# Final_Project.net
KiCad netlist of a schematic drawn in Altium Designer
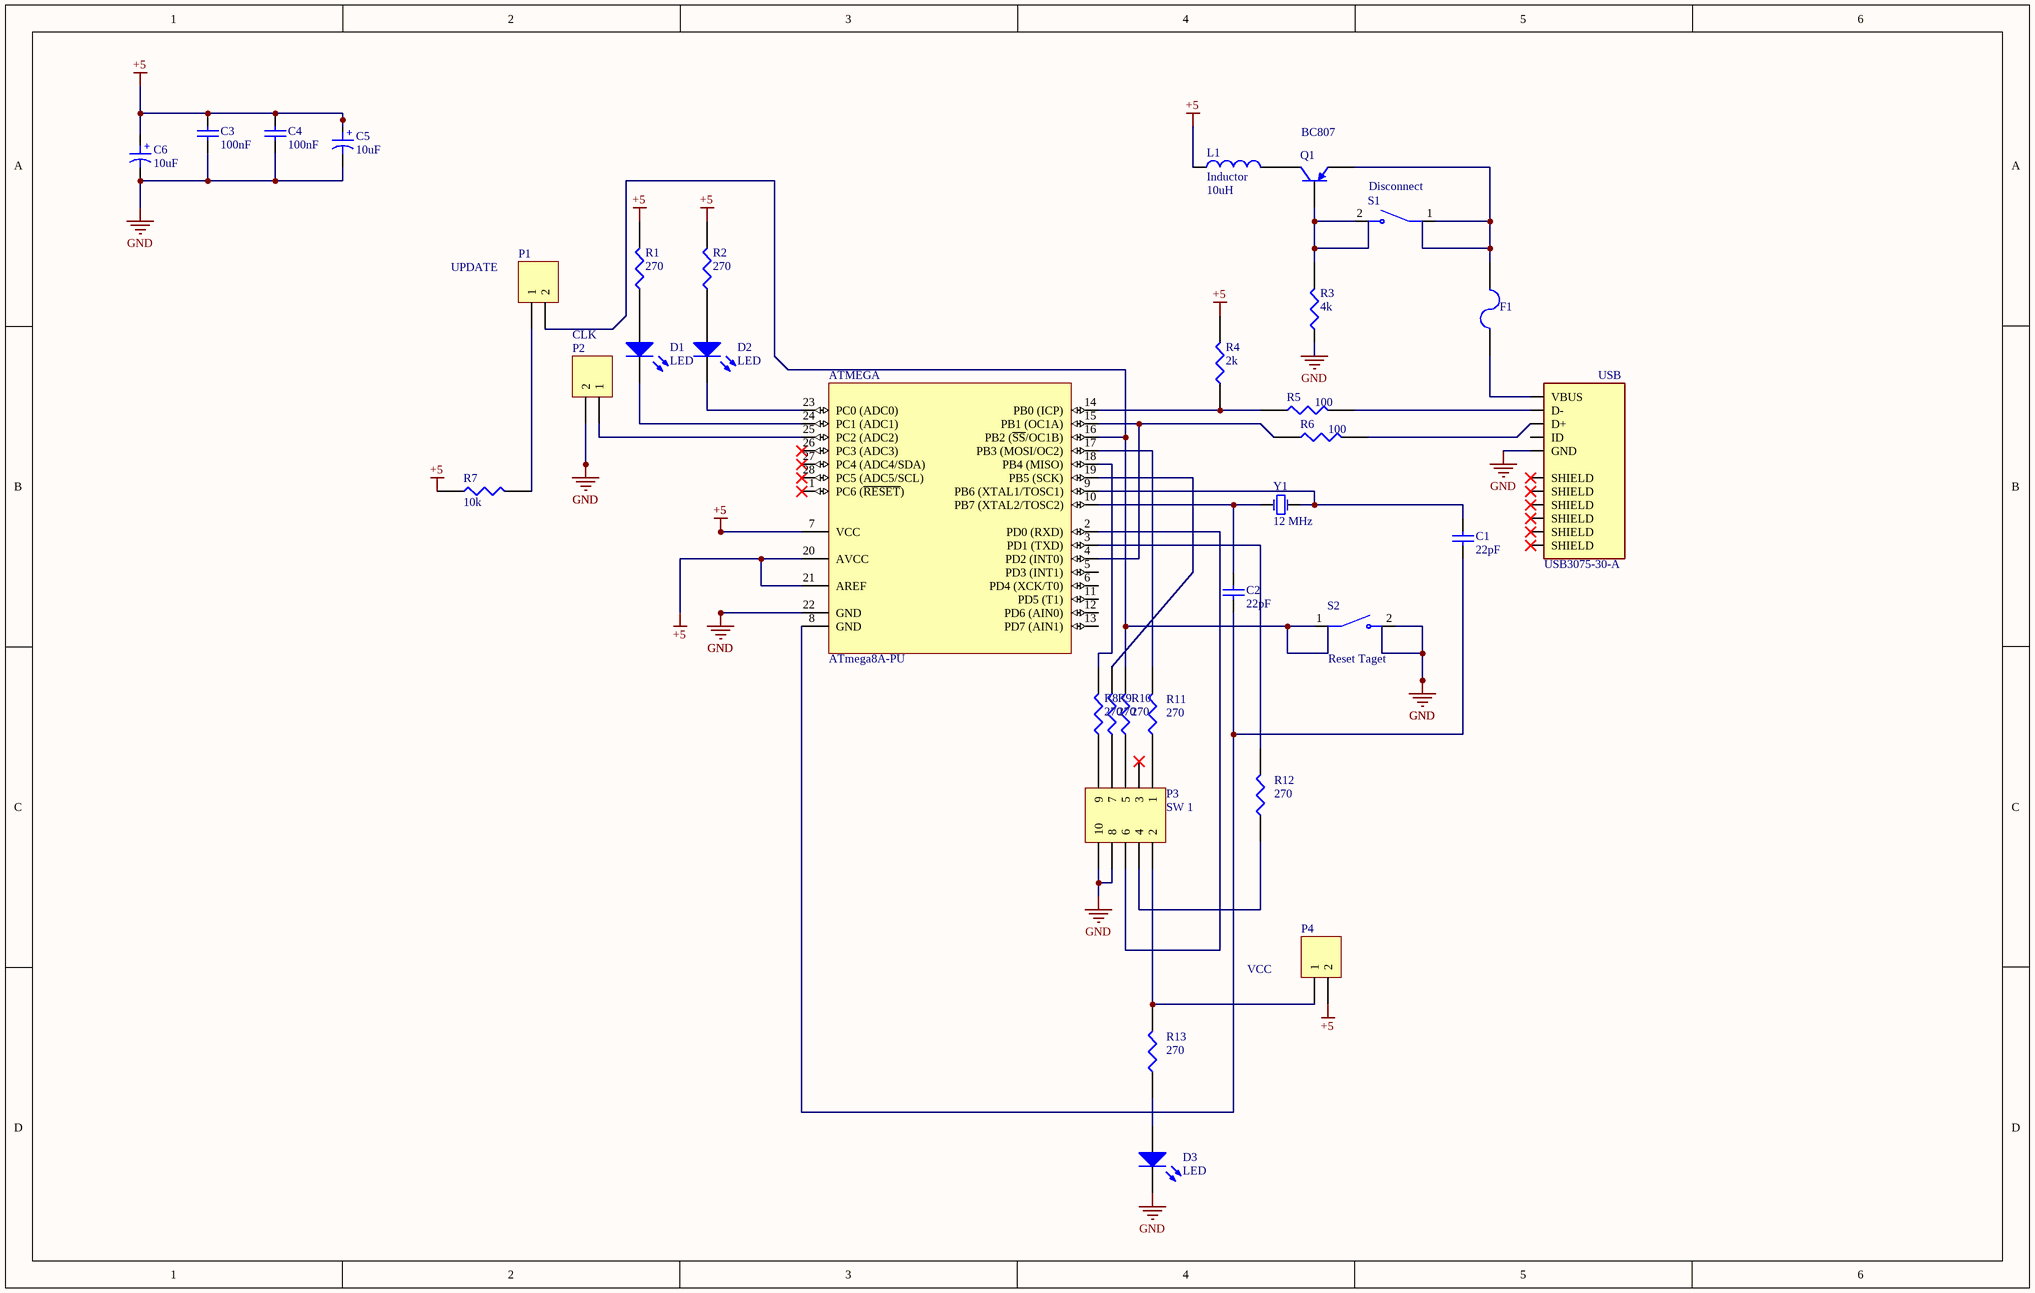
[diagram p0: Final Project.SchDoc]

(export (version "E")
  (design (tool "Eeschema 10.0.6"))
  (components
    (comp (ref "ATMEGA")
      (value "ATmega8A-PU")
      (footprint "28P3")
      (fields (field (name "PUBLISHER") "Altium Limited"))
      (libsource (lib "Atmel Microcontroller 8-Bit megaAVR") (part "ATmega8A-PU"))
    )
    (comp (ref "C1")
      (value "22pF")
      (footprint "CAPC4817X12N")
      (description "CAP 1206")
      (fields (field (name "DESIGNER") "Abbas Basereh"))
      (libsource (lib "Altium") (part "CAP SMD 1206"))
    )
    (comp (ref "C2")
      (value "22pF")
      (footprint "CAPC4817X12N")
      (description "CAP 1206")
      (fields (field (name "DESIGNER") "Abbas Basereh"))
      (libsource (lib "Altium") (part "CAP SMD 1206"))
    )
    (comp (ref "C3")
      (value "100nF")
      (footprint "CAPC4817X12N")
      (description "CAP 1206")
      (fields (field (name "DESIGNER") "Abbas Basereh"))
      (libsource (lib "Altium") (part "CAP SMD 1206"))
    )
    (comp (ref "C4")
      (value "100nF")
      (footprint "CAPC4817X12N")
      (description "CAP 1206")
      (fields (field (name "DESIGNER") "Abbas Basereh"))
      (libsource (lib "Altium") (part "CAP SMD 1206"))
    )
    (comp (ref "C5")
      (value "10uF")
      (footprint "Cap electrolitic radial 10x20-5")
      (description "Cap electrolitic radial")
      (fields (field (name "DESIGNER") "Abbas Basereh"))
      (libsource (lib "Altium") (part "Cap ELECTROLITIC TOTAL SIZE"))
    )
    (comp (ref "C6")
      (value "10uF")
      (footprint "Cap electrolitic radial 10x20-5")
      (description "Cap electrolitic radial")
      (fields (field (name "DESIGNER") "Abbas Basereh"))
      (libsource (lib "Altium") (part "Cap ELECTROLITIC TOTAL SIZE"))
    )
    (comp (ref "D1")
      (value "LED")
      (footprint "My_LED3MM")
      (description "Typical INFRARED GaAs LED")
      (fields (field (name "PUBLISHER") "Altium Limited"))
      (libsource (lib "Altium library") (part "LED"))
    )
    (comp (ref "D2")
      (value "LED")
      (footprint "My_LED3MM")
      (description "Typical INFRARED GaAs LED")
      (fields (field (name "PUBLISHER") "Altium Limited"))
      (libsource (lib "Altium library") (part "LED"))
    )
    (comp (ref "D3")
      (value "LED")
      (footprint "My_LED3MM")
      (description "Typical INFRARED GaAs LED")
      (fields (field (name "PUBLISHER") "Altium Limited"))
      (libsource (lib "Altium library") (part "LED"))
    )
    (comp (ref "F1")
      (value "F=1.0 A")
      (footprint "1206 FUSE")
      (description "SMD Fuses 1206")
      (fields (field (name "DESIGNER") "Abbas Basereh"))
      (libsource (lib "Altium") (part "Fuse SMD1206"))
    )
    (comp (ref "L1")
      (value "Inductor")
      (footprint "INDC1608L")
      (fields (field (name "ALTIUM_VALUE") "10uH") (field (name "PUBLISHER") "Altium Limited"))
      (libsource (lib "Altium") (part "Inductor"))
    )
    (comp (ref "P1")
      (value "UPDATE")
      (footprint "HDR1X2")
      (description "Header, 2-Pin")
      (fields (field (name "PUBLISHER") "Altium Limited"))
      (libsource (lib "") (part "Header 2_1"))
    )
    (comp (ref "P2")
      (value "CLK")
      (footprint "HDR1X2")
      (description "Header, 2-Pin")
      (fields (field (name "PUBLISHER") "Altium Limited"))
      (libsource (lib "Altium") (part "Header 2"))
    )
    (comp (ref "P3")
      (value "SW 1")
      (footprint "HDR2X5")
      (description "Header, 5-Pin, Dual row")
      (fields (field (name "PUBLISHER") "Altium Limited"))
      (libsource (lib "Altium") (part "Header 5X2"))
    )
    (comp (ref "P4")
      (value "VCC")
      (footprint "HDR1X2")
      (description "Header, 2-Pin")
      (fields (field (name "PUBLISHER") "Altium Limited"))
      (libsource (lib "") (part "Header 2_1"))
    )
    (comp (ref "Q1")
      (value "BC807")
      (footprint "SOT23_BEC_N")
      (description "PNP General-purpose Transistor")
      (fields (field (name "PUBLISHER") "Altium Limited"))
      (libsource (lib "Altium") (part "BC807"))
    )
    (comp (ref "R1")
      (value "270")
      (footprint "My_axial-0.4")
      (description "resistor 1/4 wat")
      (fields (field (name "Comment") "1k"))
      (libsource (lib "Altium library") (part "Res"))
    )
    (comp (ref "R2")
      (value "270")
      (footprint "RES1206")
      (description "resistor 1/4 wat")
      (fields (field (name "Comment") "1k"))
      (libsource (lib "Altium library") (part "Res"))
    )
    (comp (ref "R3")
      (value "4k")
      (footprint "My_axial-0.4")
      (description "resistor 1/4 wat")
      (fields (field (name "Comment") "1k"))
      (libsource (lib "Altium library") (part "Res"))
    )
    (comp (ref "R4")
      (value "2k")
      (footprint "My_axial-0.4")
      (description "resistor 1/4 wat")
      (fields (field (name "Comment") "1k"))
      (libsource (lib "Altium library") (part "Res"))
    )
    (comp (ref "R5")
      (value "100")
      (footprint "My_axial-0.4")
      (description "resistor 1/4 wat")
      (fields (field (name "Comment") "1k"))
      (libsource (lib "Altium library") (part "Res"))
    )
    (comp (ref "R6")
      (value "100")
      (footprint "My_axial-0.4")
      (description "resistor 1/4 wat")
      (fields (field (name "Comment") "1k"))
      (libsource (lib "Altium library") (part "Res"))
    )
    (comp (ref "R7")
      (value "10k")
      (footprint "My_axial-0.4")
      (description "resistor 1/4 wat")
      (libsource (lib "Altium library") (part "Res"))
    )
    (comp (ref "R8")
      (value "270")
      (footprint "My_axial-0.4")
      (description "resistor 1/4 wat")
      (fields (field (name "Comment") "1k"))
      (libsource (lib "Altium library") (part "Res"))
    )
    (comp (ref "R9")
      (value "270")
      (footprint "My_axial-0.4")
      (description "resistor 1/4 wat")
      (fields (field (name "Comment") "1k"))
      (libsource (lib "Altium library") (part "Res"))
    )
    (comp (ref "R10")
      (value "270")
      (footprint "My_axial-0.4")
      (description "resistor 1/4 wat")
      (fields (field (name "Comment") "1k"))
      (libsource (lib "Altium library") (part "Res"))
    )
    (comp (ref "R11")
      (value "270")
      (footprint "My_axial-0.4")
      (description "resistor 1/4 wat")
      (fields (field (name "Comment") "1k"))
      (libsource (lib "Altium library") (part "Res"))
    )
    (comp (ref "R12")
      (value "270")
      (footprint "My_axial-0.4")
      (description "resistor 1/4 wat")
      (fields (field (name "Comment") "1k"))
      (libsource (lib "Altium library") (part "Res"))
    )
    (comp (ref "R13")
      (value "270")
      (footprint "My_axial-0.4")
      (description "resistor 1/4 wat")
      (fields (field (name "Comment") "1k"))
      (libsource (lib "Altium library") (part "Res"))
    )
    (comp (ref "S1")
      (value "Disconnect")
      (footprint "SW_TL1107BF130WQ")
      (description "SWITCH TACTILE SPST-NO 0.05A 12V")
      (fields (field (name "MF") "E-Switch") (field (name "MP") "TL1107BF130WQ"))
      (libsource (lib "TL1107BF130WQ") (part "TL1107BF130WQ"))
    )
    (comp (ref "S2")
      (value "Reset Taget")
      (footprint "SW_TL1107BF130WQ")
      (description "SWITCH TACTILE SPST-NO 0.05A 12V")
      (fields (field (name "MF") "E-Switch") (field (name "MP") "TL1107BF130WQ"))
      (libsource (lib "TL1107BF130WQ") (part "TL1107BF130WQ"))
    )
    (comp (ref "USB")
      (value "USB3075-30-A")
      (footprint "GCT_USB3075-30-A")
      (fields (field (name "MF") "Global Connector Technology"))
      (libsource (lib "USB3075-30-A") (part "USB3075-30-A"))
    )
    (comp (ref "Y1")
      (value "12 MHz")
      (footprint "Crystal SMD")
      (description "XTAL Crystal")
      (fields (field (name "DESIGNER") "ABBAS BASEREH"))
      (libsource (lib "Altium") (part "XTAL"))
    )
  )
  (nets
    (net (code "1") (name "+5") (class "Default")
      (node (ref "ATMEGA") (pin "20") (pinfunction "AVCC_20") (pintype "power_in"))
      (node (ref "ATMEGA") (pin "21") (pinfunction "AREF_21") (pintype "passive"))
      (node (ref "ATMEGA") (pin "7") (pinfunction "VCC_7") (pintype "power_in"))
      (node (ref "C3") (pin "2") (pinfunction "2_2") (pintype "passive"))
      (node (ref "C4") (pin "2") (pinfunction "2_2") (pintype "passive"))
      (node (ref "C5") (pin "1") (pinfunction "1_1") (pintype "passive"))
      (node (ref "C6") (pin "1") (pinfunction "1_1") (pintype "passive"))
      (node (ref "L1") (pin "1") (pinfunction "1_1") (pintype "passive"))
      (node (ref "P4") (pin "2") (pinfunction "2_2") (pintype "passive"))
      (node (ref "R1") (pin "2") (pinfunction "2_2") (pintype "passive"))
      (node (ref "R2") (pin "2") (pinfunction "2_2") (pintype "passive"))
      (node (ref "R4") (pin "2") (pinfunction "2_2") (pintype "passive"))
      (node (ref "R7") (pin "1") (pinfunction "1_1") (pintype "passive"))
    )
    (net (code "2") (name "GND") (class "Default")
      (node (ref "ATMEGA") (pin "22") (pinfunction "GND_22") (pintype "power_in"))
      (node (ref "C3") (pin "1") (pinfunction "1_1") (pintype "passive"))
      (node (ref "C4") (pin "1") (pinfunction "1_1") (pintype "passive"))
      (node (ref "C5") (pin "2") (pinfunction "2_2") (pintype "passive"))
      (node (ref "C6") (pin "2") (pinfunction "2_2") (pintype "passive"))
      (node (ref "D3") (pin "K") (pinfunction "K_K") (pintype "passive"))
      (node (ref "P2") (pin "2") (pinfunction "2_2") (pintype "passive"))
      (node (ref "P3") (pin "10") (pinfunction "10_10") (pintype "passive"))
      (node (ref "P3") (pin "8") (pinfunction "8_8") (pintype "passive"))
      (node (ref "R3") (pin "1") (pinfunction "1_1") (pintype "passive"))
      (node (ref "S2") (pin "2") (pinfunction "2_2") (pintype "passive"))
      (node (ref "USB") (pin "5") (pinfunction "GND_5") (pintype "power_in"))
    )
    (net (code "3") (name "Net-(ATMEGA-GND-Pad8)") (class "Default")
      (node (ref "ATMEGA") (pin "8") (pinfunction "GND_8") (pintype "power_in"))
      (node (ref "C1") (pin "2") (pinfunction "2_2") (pintype "passive"))
      (node (ref "C2") (pin "2") (pinfunction "2_2") (pintype "passive"))
    )
    (net (code "4") (name "Net-(ATMEGA-PB0_(ICP))") (class "Default")
      (node (ref "ATMEGA") (pin "14") (pinfunction "PB0_(ICP)_14") (pintype "bidirectional"))
      (node (ref "R4") (pin "1") (pinfunction "1_1") (pintype "passive"))
      (node (ref "R5") (pin "1") (pinfunction "1_1") (pintype "passive"))
    )
    (net (code "5") (name "Net-(ATMEGA-PB1_(OC1A))") (class "Default")
      (node (ref "ATMEGA") (pin "15") (pinfunction "PB1_(OC1A)_15") (pintype "bidirectional"))
      (node (ref "ATMEGA") (pin "4") (pinfunction "PD2_(INT0)_4") (pintype "bidirectional"))
      (node (ref "R6") (pin "1") (pinfunction "1_1") (pintype "passive"))
    )
    (net (code "6") (name "Net-(ATMEGA-PB2_(~{SS}{slash}OC1B))") (class "Default")
      (node (ref "ATMEGA") (pin "16") (pinfunction "PB2_(~{SS}/OC1B)_16") (pintype "bidirectional"))
      (node (ref "P1") (pin "2") (pinfunction "2_2") (pintype "passive"))
      (node (ref "R10") (pin "2") (pinfunction "2_2") (pintype "passive"))
      (node (ref "S2") (pin "1") (pinfunction "1_1") (pintype "passive"))
    )
    (net (code "7") (name "Net-(ATMEGA-PB3_(MOSI{slash}OC2))") (class "Default")
      (node (ref "ATMEGA") (pin "17") (pinfunction "PB3_(MOSI/OC2)_17") (pintype "bidirectional"))
      (node (ref "R11") (pin "2") (pinfunction "2_2") (pintype "passive"))
    )
    (net (code "8") (name "Net-(ATMEGA-PB4_(MISO))") (class "Default")
      (node (ref "ATMEGA") (pin "18") (pinfunction "PB4_(MISO)_18") (pintype "bidirectional"))
      (node (ref "R8") (pin "2") (pinfunction "2_2") (pintype "passive"))
    )
    (net (code "9") (name "Net-(ATMEGA-PB5_(SCK))") (class "Default")
      (node (ref "ATMEGA") (pin "19") (pinfunction "PB5_(SCK)_19") (pintype "bidirectional"))
      (node (ref "R9") (pin "2") (pinfunction "2_2") (pintype "passive"))
    )
    (net (code "10") (name "Net-(ATMEGA-PB6_(XTAL1{slash}TOSC1))") (class "Default")
      (node (ref "ATMEGA") (pin "9") (pinfunction "PB6_(XTAL1/TOSC1)_9") (pintype "bidirectional"))
      (node (ref "C1") (pin "1") (pinfunction "1_1") (pintype "passive"))
      (node (ref "Y1") (pin "2") (pinfunction "OSC2_2") (pintype "passive"))
    )
    (net (code "11") (name "Net-(ATMEGA-PB7_(XTAL2{slash}TOSC2))") (class "Default")
      (node (ref "ATMEGA") (pin "10") (pinfunction "PB7_(XTAL2/TOSC2)_10") (pintype "bidirectional"))
      (node (ref "C2") (pin "1") (pinfunction "1_1") (pintype "passive"))
      (node (ref "Y1") (pin "1") (pinfunction "OSC1_1") (pintype "passive"))
    )
    (net (code "12") (name "Net-(ATMEGA-PC0_(ADC0))") (class "Default")
      (node (ref "ATMEGA") (pin "23") (pinfunction "PC0_(ADC0)_23") (pintype "bidirectional"))
      (node (ref "D2") (pin "K") (pinfunction "K_K") (pintype "passive"))
    )
    (net (code "13") (name "Net-(ATMEGA-PC1_(ADC1))") (class "Default")
      (node (ref "ATMEGA") (pin "24") (pinfunction "PC1_(ADC1)_24") (pintype "bidirectional"))
      (node (ref "D1") (pin "K") (pinfunction "K_K") (pintype "passive"))
    )
    (net (code "14") (name "Net-(ATMEGA-PC2_(ADC2))") (class "Default")
      (node (ref "ATMEGA") (pin "25") (pinfunction "PC2_(ADC2)_25") (pintype "bidirectional"))
      (node (ref "P2") (pin "1") (pinfunction "1_1") (pintype "passive"))
    )
    (net (code "15") (name "Net-(ATMEGA-PD0_(RXD))") (class "Default")
      (node (ref "ATMEGA") (pin "2") (pinfunction "PD0_(RXD)_2") (pintype "bidirectional"))
      (node (ref "P3") (pin "6") (pinfunction "6_6") (pintype "passive"))
    )
    (net (code "16") (name "Net-(ATMEGA-PD1_(TXD))") (class "Default")
      (node (ref "ATMEGA") (pin "3") (pinfunction "PD1_(TXD)_3") (pintype "bidirectional"))
      (node (ref "R12") (pin "2") (pinfunction "2_2") (pintype "passive"))
    )
    (net (code "17") (name "Net-(D1-PadA)") (class "Default")
      (node (ref "D1") (pin "A") (pinfunction "A_A") (pintype "passive"))
      (node (ref "R1") (pin "1") (pinfunction "1_1") (pintype "passive"))
    )
    (net (code "18") (name "Net-(D2-PadA)") (class "Default")
      (node (ref "D2") (pin "A") (pinfunction "A_A") (pintype "passive"))
      (node (ref "R2") (pin "1") (pinfunction "1_1") (pintype "passive"))
    )
    (net (code "19") (name "Net-(D3-PadA)") (class "Default")
      (node (ref "D3") (pin "A") (pinfunction "A_A") (pintype "passive"))
      (node (ref "R13") (pin "1") (pinfunction "1_1") (pintype "passive"))
    )
    (net (code "20") (name "Net-(P1-Pad1)") (class "Default")
      (node (ref "P1") (pin "1") (pinfunction "1_1") (pintype "passive"))
      (node (ref "R7") (pin "2") (pinfunction "2_2") (pintype "passive"))
    )
    (net (code "21") (name "Net-(P3-Pad1)") (class "Default")
      (node (ref "P3") (pin "1") (pinfunction "1_1") (pintype "passive"))
      (node (ref "R11") (pin "1") (pinfunction "1_1") (pintype "passive"))
    )
    (net (code "22") (name "Net-(P3-Pad2)") (class "Default")
      (node (ref "P3") (pin "2") (pinfunction "2_2") (pintype "passive"))
      (node (ref "P4") (pin "1") (pinfunction "1_1") (pintype "passive"))
      (node (ref "R13") (pin "2") (pinfunction "2_2") (pintype "passive"))
    )
    (net (code "23") (name "Net-(P3-Pad4)") (class "Default")
      (node (ref "P3") (pin "4") (pinfunction "4_4") (pintype "passive"))
      (node (ref "R12") (pin "1") (pinfunction "1_1") (pintype "passive"))
    )
    (net (code "24") (name "Net-(P3-Pad5)") (class "Default")
      (node (ref "P3") (pin "5") (pinfunction "5_5") (pintype "passive"))
      (node (ref "R10") (pin "1") (pinfunction "1_1") (pintype "passive"))
    )
    (net (code "25") (name "Net-(P3-Pad7)") (class "Default")
      (node (ref "P3") (pin "7") (pinfunction "7_7") (pintype "passive"))
      (node (ref "R9") (pin "1") (pinfunction "1_1") (pintype "passive"))
    )
    (net (code "26") (name "Net-(P3-Pad9)") (class "Default")
      (node (ref "P3") (pin "9") (pinfunction "9_9") (pintype "passive"))
      (node (ref "R8") (pin "1") (pinfunction "1_1") (pintype "passive"))
    )
    (net (code "27") (name "Net-(Q1-B)") (class "Default")
      (node (ref "Q1") (pin "1") (pinfunction "B_1") (pintype "passive"))
      (node (ref "R3") (pin "2") (pinfunction "2_2") (pintype "passive"))
      (node (ref "S1") (pin "2") (pinfunction "2_2") (pintype "passive"))
    )
    (net (code "28") (name "Net-(Q1-C)") (class "Default")
      (node (ref "L1") (pin "2") (pinfunction "2_2") (pintype "passive"))
      (node (ref "Q1") (pin "3") (pinfunction "C_3") (pintype "passive"))
    )
    (net (code "29") (name "Net-(Q1-E)") (class "Default")
      (node (ref "F1") (pin "2") (pinfunction "2_2") (pintype "passive"))
      (node (ref "Q1") (pin "2") (pinfunction "E_2") (pintype "passive"))
      (node (ref "S1") (pin "1") (pinfunction "1_1") (pintype "passive"))
    )
    (net (code "30") (name "Net-(USB-D+)") (class "Default")
      (node (ref "R6") (pin "2") (pinfunction "2_2") (pintype "passive"))
      (node (ref "USB") (pin "3") (pinfunction "D+_3") (pintype "bidirectional"))
    )
    (net (code "31") (name "Net-(USB-D-)") (class "Default")
      (node (ref "R5") (pin "2") (pinfunction "2_2") (pintype "passive"))
      (node (ref "USB") (pin "2") (pinfunction "D-_2") (pintype "bidirectional"))
    )
    (net (code "32") (name "Net-(USB-VBUS)") (class "Default")
      (node (ref "F1") (pin "1") (pinfunction "1_1") (pintype "passive"))
      (node (ref "USB") (pin "1") (pinfunction "VBUS_1") (pintype "power_in"))
    )
    (net (code "33") (name "unconnected-(ATMEGA-PC3_(ADC3)-Pad26)") (class "Default")
      (node (ref "ATMEGA") (pin "26") (pinfunction "PC3_(ADC3)_26") (pintype "bidirectional+no_connect"))
    )
    (net (code "34") (name "unconnected-(ATMEGA-PC4_(ADC4{slash}SDA)-Pad27)") (class "Default")
      (node (ref "ATMEGA") (pin "27") (pinfunction "PC4_(ADC4/SDA)_27") (pintype "bidirectional+no_connect"))
    )
    (net (code "35") (name "unconnected-(ATMEGA-PC5_(ADC5{slash}SCL)-Pad28)") (class "Default")
      (node (ref "ATMEGA") (pin "28") (pinfunction "PC5_(ADC5/SCL)_28") (pintype "bidirectional+no_connect"))
    )
    (net (code "36") (name "unconnected-(ATMEGA-PC6_(~{RESET})-Pad1)") (class "Default")
      (node (ref "ATMEGA") (pin "1") (pinfunction "PC6_(~{RESET})_1") (pintype "bidirectional+no_connect"))
    )
    (net (code "37") (name "unconnected-(ATMEGA-PD3_(INT1)-Pad5)") (class "Default")
      (node (ref "ATMEGA") (pin "5") (pinfunction "PD3_(INT1)_5") (pintype "bidirectional"))
    )
    (net (code "38") (name "unconnected-(ATMEGA-PD4_(XCK{slash}T0)-Pad6)") (class "Default")
      (node (ref "ATMEGA") (pin "6") (pinfunction "PD4_(XCK/T0)_6") (pintype "bidirectional"))
    )
    (net (code "39") (name "unconnected-(ATMEGA-PD5_(T1)-Pad11)") (class "Default")
      (node (ref "ATMEGA") (pin "11") (pinfunction "PD5_(T1)_11") (pintype "bidirectional"))
    )
    (net (code "40") (name "unconnected-(ATMEGA-PD6_(AIN0)-Pad12)") (class "Default")
      (node (ref "ATMEGA") (pin "12") (pinfunction "PD6_(AIN0)_12") (pintype "bidirectional"))
    )
    (net (code "41") (name "unconnected-(ATMEGA-PD7_(AIN1)-Pad13)") (class "Default")
      (node (ref "ATMEGA") (pin "13") (pinfunction "PD7_(AIN1)_13") (pintype "bidirectional"))
    )
    (net (code "42") (name "unconnected-(P3-Pad3)") (class "Default")
      (node (ref "P3") (pin "3") (pinfunction "3_3") (pintype "passive+no_connect"))
    )
    (net (code "43") (name "unconnected-(USB-ID-Pad4)") (class "Default")
      (node (ref "USB") (pin "4") (pinfunction "ID_4") (pintype "bidirectional"))
    )
    (net (code "44") (name "unconnected-(USB-SHIELD-PadS1)") (class "Default")
      (node (ref "USB") (pin "S1") (pinfunction "SHIELD_S1") (pintype "passive+no_connect"))
    )
    (net (code "45") (name "unconnected-(USB-SHIELD-PadS2)") (class "Default")
      (node (ref "USB") (pin "S2") (pinfunction "SHIELD_S2") (pintype "passive+no_connect"))
    )
    (net (code "46") (name "unconnected-(USB-SHIELD-PadS3)") (class "Default")
      (node (ref "USB") (pin "S3") (pinfunction "SHIELD_S3") (pintype "passive+no_connect"))
    )
    (net (code "47") (name "unconnected-(USB-SHIELD-PadS4)") (class "Default")
      (node (ref "USB") (pin "S4") (pinfunction "SHIELD_S4") (pintype "passive+no_connect"))
    )
    (net (code "48") (name "unconnected-(USB-SHIELD-PadS5)") (class "Default")
      (node (ref "USB") (pin "S5") (pinfunction "SHIELD_S5") (pintype "passive+no_connect"))
    )
    (net (code "49") (name "unconnected-(USB-SHIELD-PadS6)") (class "Default")
      (node (ref "USB") (pin "S6") (pinfunction "SHIELD_S6") (pintype "passive+no_connect"))
    )
  )
)
